# piezo-jfet-buffer-simple-set-resistor.net
KiCad netlist of a schematic drawn in EAGLE
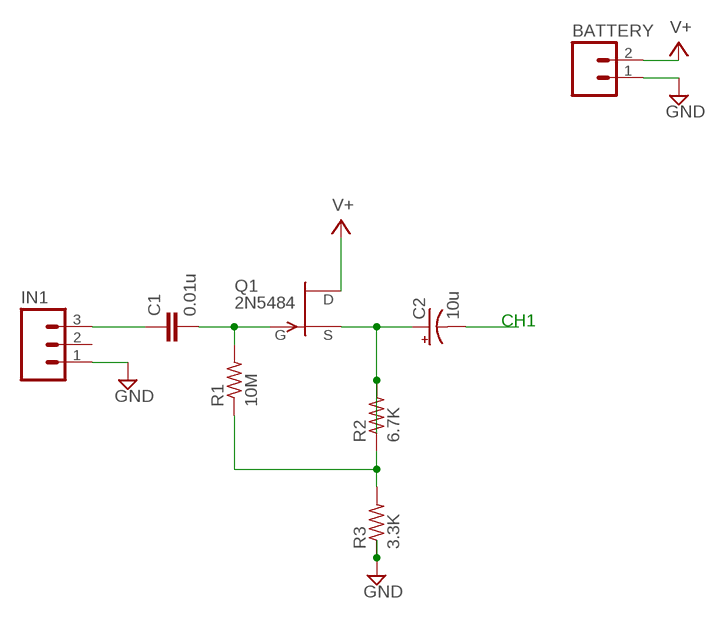
[diagram p0: schematic, sheet 1]

(export (version "E")
  (design (tool "Eeschema 10.0.6"))
  (components
    (comp (ref "BATTERY")
      (value "M02PTH")
      (footprint "eagle-import:1X02")
      (libsource (lib "eagle-import") (part "M02PTH"))
    )
    (comp (ref "C1")
      (value "0.01u")
      (footprint "eagle-import:C5B3")
      (libsource (lib "eagle-import") (part "C5/3"))
    )
    (comp (ref "C2")
      (value "10u")
      (footprint "eagle-import:CPOL-RADIAL-10UF-25V")
      (libsource (lib "eagle-import") (part "CAP_POLPTH2"))
    )
    (comp (ref "IN1")
      (value "M03LOCK")
      (footprint "eagle-import:1X03_LOCK")
      (libsource (lib "eagle-import") (part "M03LOCK"))
    )
    (comp (ref "Q1")
      (value "2N5484")
      (footprint "eagle-import:TO92-")
      (libsource (lib "eagle-import") (part "?5482N4"))
    )
    (comp (ref "R1")
      (value "10M")
      (footprint "eagle-import:0414V")
      (libsource (lib "eagle-import") (part "R-US_0414/5V"))
    )
    (comp (ref "R2")
      (value "6.7K")
      (footprint "eagle-import:0414V")
      (libsource (lib "eagle-import") (part "R-US_0414/5V"))
    )
    (comp (ref "R3")
      (value "3.3K")
      (footprint "eagle-import:0414V")
      (libsource (lib "eagle-import") (part "R-US_0414/5V"))
    )
  )
  (nets
    (net (code "1") (name "GND") (class "Default")
      (node (ref "BATTERY") (pin "1") (pinfunction "1_1") (pintype "passive"))
      (node (ref "IN1") (pin "1") (pinfunction "1_1") (pintype "passive"))
      (node (ref "R3") (pin "1") (pinfunction "1_1") (pintype "passive"))
    )
    (net (code "2") (name "Net-(C1-Pad1)") (class "Default")
      (node (ref "C1") (pin "1") (pinfunction "1_1") (pintype "passive"))
      (node (ref "IN1") (pin "3") (pinfunction "3_3") (pintype "passive"))
    )
    (net (code "3") (name "Net-(C2-+)") (class "Default")
      (node (ref "C2") (pin "1") (pinfunction "+_1") (pintype "passive"))
      (node (ref "Q1") (pin "2") (pinfunction "S_2") (pintype "passive"))
      (node (ref "R2") (pin "2") (pinfunction "2_2") (pintype "passive"))
    )
    (net (code "4") (name "Net-(Q1-G)") (class "Default")
      (node (ref "C1") (pin "2") (pinfunction "2_2") (pintype "passive"))
      (node (ref "Q1") (pin "1") (pinfunction "G_1") (pintype "passive"))
      (node (ref "R1") (pin "2") (pinfunction "2_2") (pintype "passive"))
    )
    (net (code "5") (name "Net-(R1-Pad1)") (class "Default")
      (node (ref "R1") (pin "1") (pinfunction "1_1") (pintype "passive"))
      (node (ref "R2") (pin "1") (pinfunction "1_1") (pintype "passive"))
      (node (ref "R3") (pin "2") (pinfunction "2_2") (pintype "passive"))
    )
    (net (code "6") (name "V+") (class "Default")
      (node (ref "BATTERY") (pin "2") (pinfunction "2_2") (pintype "passive"))
      (node (ref "Q1") (pin "3") (pinfunction "D_3") (pintype "passive"))
    )
    (net (code "7") (name "unconnected-(C2---Pad2)") (class "Default")
      (node (ref "C2") (pin "2") (pinfunction "-_2") (pintype "passive"))
    )
    (net (code "8") (name "unconnected-(IN1-Pad2)") (class "Default")
      (node (ref "IN1") (pin "2") (pinfunction "2_2") (pintype "passive"))
    )
  )
)
